# Pmod_8LD.net
KiCad netlist of a schematic drawn in Altium Designer
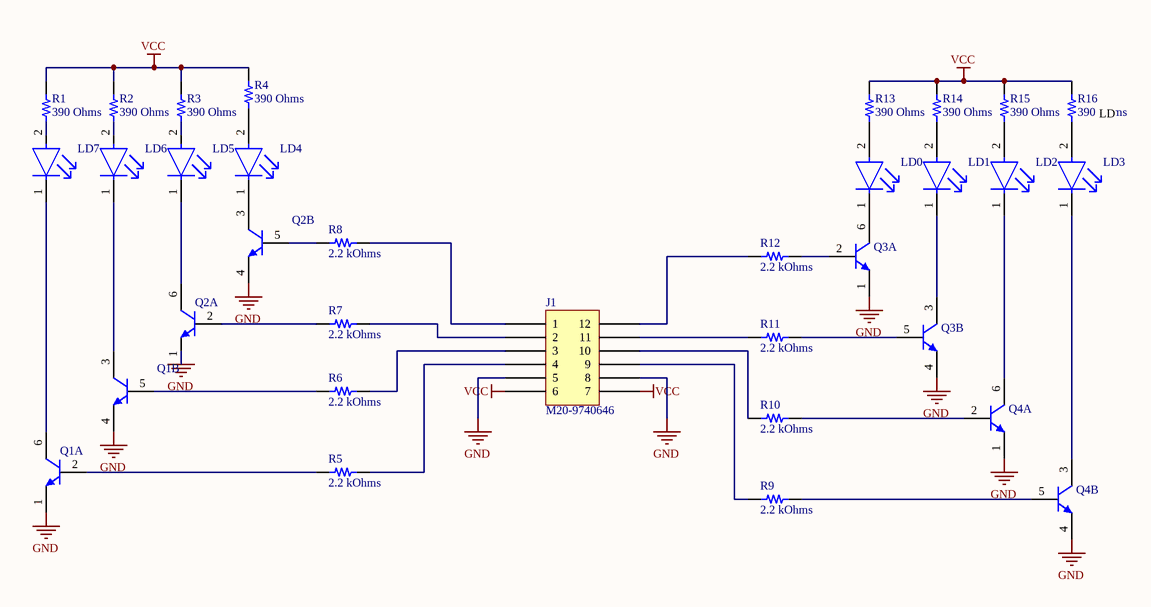
[diagram p0: Pmod_8LD.SchDoc]

(export (version "E")
  (design (tool "Eeschema 10.0.6"))
  (components
    (comp (ref "J1")
      (value "M20-9740646")
      (footprint "HARWIN M20-9740645")
      (description "CONN HEADER R/A 12POS 2.54MM")
      (fields (field (name "MANUFACTURER") "Harwin Inc."))
      (libsource (lib "Celestial Altium Library - altium_library") (part "2X6 PIN DU"))
    )
    (comp (ref "LD0")
      (value "HSMG-C191")
      (footprint "FP-HSMG-C191-MFG")
      (description "LED GREEN DIFFUSED CHIP SMD")
      (fields
        (field (name "MANUFACTURER") "Broadcom")
        (field (name "OCTOPART") "https://octopart.com/hsmg-c191-broadcom-71131308")
      )
      (libsource (lib "Altium Content Vault") (part "8706943c75ba83719d021d2fdc84c58"))
    )
    (comp (ref "LD1")
      (value "HSMG-C191")
      (footprint "FP-HSMG-C191-MFG")
      (description "LED GREEN DIFFUSED CHIP SMD")
      (fields
        (field (name "MANUFACTURER") "Broadcom")
        (field (name "OCTOPART") "https://octopart.com/hsmg-c191-broadcom-71131308")
      )
      (libsource (lib "Altium Content Vault") (part "8706943c75ba83719d021d2fdc84c58"))
    )
    (comp (ref "LD2")
      (value "HSMG-C191")
      (footprint "FP-HSMG-C191-MFG")
      (description "LED GREEN DIFFUSED CHIP SMD")
      (fields
        (field (name "MANUFACTURER") "Broadcom")
        (field (name "OCTOPART") "https://octopart.com/hsmg-c191-broadcom-71131308")
      )
      (libsource (lib "Altium Content Vault") (part "8706943c75ba83719d021d2fdc84c58"))
    )
    (comp (ref "LD3")
      (value "HSMG-C191")
      (footprint "FP-HSMG-C191-MFG")
      (description "LED GREEN DIFFUSED CHIP SMD")
      (fields
        (field (name "MANUFACTURER") "Broadcom")
        (field (name "OCTOPART") "https://octopart.com/hsmg-c191-broadcom-71131308")
      )
      (libsource (lib "Altium Content Vault") (part "8706943c75ba83719d021d2fdc84c58"))
    )
    (comp (ref "LD4")
      (value "HSMG-C191")
      (footprint "FP-HSMG-C191-MFG")
      (description "LED GREEN DIFFUSED CHIP SMD")
      (fields
        (field (name "MANUFACTURER") "Broadcom")
        (field (name "OCTOPART") "https://octopart.com/hsmg-c191-broadcom-71131308")
      )
      (libsource (lib "Altium Content Vault") (part "8706943c75ba83719d021d2fdc84c58"))
    )
    (comp (ref "LD5")
      (value "HSMG-C191")
      (footprint "FP-HSMG-C191-MFG")
      (description "LED GREEN DIFFUSED CHIP SMD")
      (fields
        (field (name "MANUFACTURER") "Broadcom")
        (field (name "OCTOPART") "https://octopart.com/hsmg-c191-broadcom-71131308")
      )
      (libsource (lib "Altium Content Vault") (part "8706943c75ba83719d021d2fdc84c58"))
    )
    (comp (ref "LD6")
      (value "HSMG-C191")
      (footprint "FP-HSMG-C191-MFG")
      (description "LED GREEN DIFFUSED CHIP SMD")
      (fields
        (field (name "MANUFACTURER") "Broadcom")
        (field (name "OCTOPART") "https://octopart.com/hsmg-c191-broadcom-71131308")
      )
      (libsource (lib "Altium Content Vault") (part "8706943c75ba83719d021d2fdc84c58"))
    )
    (comp (ref "LD7")
      (value "HSMG-C191")
      (footprint "FP-HSMG-C191-MFG")
      (description "LED GREEN DIFFUSED CHIP SMD")
      (fields
        (field (name "MANUFACTURER") "Broadcom")
        (field (name "OCTOPART") "https://octopart.com/hsmg-c191-broadcom-71131308")
      )
      (libsource (lib "Altium Content Vault") (part "8706943c75ba83719d021d2fdc84c58"))
    )
    (comp (ref "Q1")
      (value "BC846BDW1T1G")
      (footprint "ONSC-SOT-363-6-419B-02_W_V")
      (description "Dual General Purpose Transistors, NPN, 6-Pin SOT-363, Pb-Free, Tape and Reel")
      (fields (field (name "MANUFACTURER") "On Semiconductor"))
      (libsource (lib "Altium Content Vault") (part "ONSC-NPN_NPN-6_F"))
    )
    (comp (ref "Q2")
      (value "BC846BDW1T1G")
      (footprint "ONSC-SOT-363-6-419B-02_W_V")
      (description "Dual General Purpose Transistors, NPN, 6-Pin SOT-363, Pb-Free, Tape and Reel")
      (fields (field (name "MANUFACTURER") "On Semiconductor"))
      (libsource (lib "Altium Content Vault") (part "ONSC-NPN_NPN-6_F"))
    )
    (comp (ref "Q3")
      (value "BC846BDW1T1G")
      (footprint "ONSC-SOT-363-6-419B-02_W_V")
      (description "Dual General Purpose Transistors, NPN, 6-Pin SOT-363, Pb-Free, Tape and Reel")
      (fields (field (name "MANUFACTURER") "On Semiconductor"))
      (libsource (lib "Altium Content Vault") (part "ONSC-NPN_NPN-6_F"))
    )
    (comp (ref "Q4")
      (value "BC846BDW1T1G")
      (footprint "ONSC-SOT-363-6-419B-02_W_V")
      (description "Dual General Purpose Transistors, NPN, 6-Pin SOT-363, Pb-Free, Tape and Reel")
      (fields (field (name "MANUFACTURER") "On Semiconductor"))
      (libsource (lib "Altium Content Vault") (part "ONSC-NPN_NPN-6_F"))
    )
    (comp (ref "R1")
      (value "390 Ohms")
      (footprint "RES 0805_2012")
      (description "RES SMD 390 OHM 5% 1/8W 0805")
      (fields (field (name "PART NUMBER") "AC0805JR-07390RL") (field (name "MANUFACTURER") "Yageo"))
      (libsource (lib "Celestial Altium Library - altium_library") (part "Resistor"))
    )
    (comp (ref "R2")
      (value "390 Ohms")
      (footprint "RES 0805_2012")
      (description "RES SMD 390 OHM 5% 1/8W 0805")
      (fields (field (name "PART NUMBER") "AC0805JR-07390RL") (field (name "MANUFACTURER") "Yageo"))
      (libsource (lib "Celestial Altium Library - altium_library") (part "Resistor"))
    )
    (comp (ref "R3")
      (value "390 Ohms")
      (footprint "RES 0805_2012")
      (description "RES SMD 390 OHM 5% 1/8W 0805")
      (fields (field (name "PART NUMBER") "AC0805JR-07390RL") (field (name "MANUFACTURER") "Yageo"))
      (libsource (lib "Celestial Altium Library - altium_library") (part "Resistor"))
    )
    (comp (ref "R4")
      (value "390 Ohms")
      (footprint "RES 0805_2012")
      (description "RES SMD 390 OHM 5% 1/8W 0805")
      (fields (field (name "PART NUMBER") "AC0805JR-07390RL") (field (name "MANUFACTURER") "Yageo"))
      (libsource (lib "Celestial Altium Library - altium_library") (part "Resistor"))
    )
    (comp (ref "R5")
      (value "2.2 kOhms")
      (footprint "RES 0805_2012")
      (description "RES SMD 2.2KOHM 0.01% 1/10W 0805")
      (fields (field (name "PART NUMBER") "RG2012L-222-L-T05") (field (name "MANUFACTURER") "Susumu"))
      (libsource (lib "Celestial Altium Library - altium_library") (part "Resistor"))
    )
    (comp (ref "R6")
      (value "2.2 kOhms")
      (footprint "RES 0805_2012")
      (description "RES SMD 2.2KOHM 0.01% 1/10W 0805")
      (fields (field (name "PART NUMBER") "RG2012L-222-L-T05") (field (name "MANUFACTURER") "Susumu"))
      (libsource (lib "Celestial Altium Library - altium_library") (part "Resistor"))
    )
    (comp (ref "R7")
      (value "2.2 kOhms")
      (footprint "RES 0805_2012")
      (description "RES SMD 2.2KOHM 0.01% 1/10W 0805")
      (fields (field (name "PART NUMBER") "RG2012L-222-L-T05") (field (name "MANUFACTURER") "Susumu"))
      (libsource (lib "Celestial Altium Library - altium_library") (part "Resistor"))
    )
    (comp (ref "R8")
      (value "2.2 kOhms")
      (footprint "RES 0805_2012")
      (description "RES SMD 2.2KOHM 0.01% 1/10W 0805")
      (fields (field (name "PART NUMBER") "RG2012L-222-L-T05") (field (name "MANUFACTURER") "Susumu"))
      (libsource (lib "Celestial Altium Library - altium_library") (part "Resistor"))
    )
    (comp (ref "R9")
      (value "2.2 kOhms")
      (footprint "RES 0805_2012")
      (description "RES SMD 2.2KOHM 0.01% 1/10W 0805")
      (fields (field (name "PART NUMBER") "RG2012L-222-L-T05") (field (name "MANUFACTURER") "Susumu"))
      (libsource (lib "Celestial Altium Library - altium_library") (part "Resistor"))
    )
    (comp (ref "R10")
      (value "2.2 kOhms")
      (footprint "RES 0805_2012")
      (description "RES SMD 2.2KOHM 0.01% 1/10W 0805")
      (fields (field (name "PART NUMBER") "RG2012L-222-L-T05") (field (name "MANUFACTURER") "Susumu"))
      (libsource (lib "Celestial Altium Library - altium_library") (part "Resistor"))
    )
    (comp (ref "R11")
      (value "2.2 kOhms")
      (footprint "RES 0805_2012")
      (description "RES SMD 2.2KOHM 0.01% 1/10W 0805")
      (fields (field (name "PART NUMBER") "RG2012L-222-L-T05") (field (name "MANUFACTURER") "Susumu"))
      (libsource (lib "Celestial Altium Library - altium_library") (part "Resistor"))
    )
    (comp (ref "R12")
      (value "2.2 kOhms")
      (footprint "RES 0805_2012")
      (description "RES SMD 2.2KOHM 0.01% 1/10W 0805")
      (fields (field (name "PART NUMBER") "RG2012L-222-L-T05") (field (name "MANUFACTURER") "Susumu"))
      (libsource (lib "Celestial Altium Library - altium_library") (part "Resistor"))
    )
    (comp (ref "R13")
      (value "390 Ohms")
      (footprint "RES 0805_2012")
      (description "RES SMD 390 OHM 5% 1/8W 0805")
      (fields (field (name "PART NUMBER") "AC0805JR-07390RL") (field (name "MANUFACTURER") "Yageo"))
      (libsource (lib "Celestial Altium Library - altium_library") (part "Resistor"))
    )
    (comp (ref "R14")
      (value "390 Ohms")
      (footprint "RES 0805_2012")
      (description "RES SMD 390 OHM 5% 1/8W 0805")
      (fields (field (name "PART NUMBER") "AC0805JR-07390RL") (field (name "MANUFACTURER") "Yageo"))
      (libsource (lib "Celestial Altium Library - altium_library") (part "Resistor"))
    )
    (comp (ref "R15")
      (value "390 Ohms")
      (footprint "RES 0805_2012")
      (description "RES SMD 390 OHM 5% 1/8W 0805")
      (fields (field (name "PART NUMBER") "AC0805JR-07390RL") (field (name "MANUFACTURER") "Yageo"))
      (libsource (lib "Celestial Altium Library - altium_library") (part "Resistor"))
    )
    (comp (ref "R16")
      (value "390 Ohms")
      (footprint "RES 0805_2012")
      (description "RES SMD 390 OHM 5% 1/8W 0805")
      (fields (field (name "PART NUMBER") "AC0805JR-07390RL") (field (name "MANUFACTURER") "Yageo"))
      (libsource (lib "Celestial Altium Library - altium_library") (part "Resistor"))
    )
  )
  (nets
    (net (code "1") (name "GND") (class "Default")
      (node (ref "J1") (pin "5") (pinfunction "5_5") (pintype "passive"))
      (node (ref "J1") (pin "8") (pinfunction "8_8") (pintype "passive"))
      (node (ref "Q1") (pin "1") (pinfunction "E_1") (pintype "passive"))
      (node (ref "Q1") (pin "4") (pinfunction "E_4") (pintype "passive"))
      (node (ref "Q2") (pin "1") (pinfunction "E_1") (pintype "passive"))
      (node (ref "Q2") (pin "4") (pinfunction "E_4") (pintype "passive"))
      (node (ref "Q3") (pin "1") (pinfunction "E_1") (pintype "passive"))
      (node (ref "Q3") (pin "4") (pinfunction "E_4") (pintype "passive"))
      (node (ref "Q4") (pin "1") (pinfunction "E_1") (pintype "passive"))
      (node (ref "Q4") (pin "4") (pinfunction "E_4") (pintype "passive"))
    )
    (net (code "2") (name "Net-(J1-Pad1)") (class "Default")
      (node (ref "J1") (pin "1") (pinfunction "1_1") (pintype "passive"))
      (node (ref "R8") (pin "1") (pinfunction "1_1") (pintype "passive"))
    )
    (net (code "3") (name "Net-(J1-Pad2)") (class "Default")
      (node (ref "J1") (pin "2") (pinfunction "2_2") (pintype "passive"))
      (node (ref "R7") (pin "1") (pinfunction "1_1") (pintype "passive"))
    )
    (net (code "4") (name "Net-(J1-Pad3)") (class "Default")
      (node (ref "J1") (pin "3") (pinfunction "3_3") (pintype "passive"))
      (node (ref "R6") (pin "1") (pinfunction "1_1") (pintype "passive"))
    )
    (net (code "5") (name "Net-(J1-Pad4)") (class "Default")
      (node (ref "J1") (pin "4") (pinfunction "4_4") (pintype "passive"))
      (node (ref "R5") (pin "1") (pinfunction "1_1") (pintype "passive"))
    )
    (net (code "6") (name "Net-(J1-Pad9)") (class "Default")
      (node (ref "J1") (pin "9") (pinfunction "9_9") (pintype "passive"))
      (node (ref "R9") (pin "2") (pinfunction "2_2") (pintype "passive"))
    )
    (net (code "7") (name "Net-(J1-Pad10)") (class "Default")
      (node (ref "J1") (pin "10") (pinfunction "10_10") (pintype "passive"))
      (node (ref "R10") (pin "2") (pinfunction "2_2") (pintype "passive"))
    )
    (net (code "8") (name "Net-(J1-Pad11)") (class "Default")
      (node (ref "J1") (pin "11") (pinfunction "11_11") (pintype "passive"))
      (node (ref "R11") (pin "2") (pinfunction "2_2") (pintype "passive"))
    )
    (net (code "9") (name "Net-(J1-Pad12)") (class "Default")
      (node (ref "J1") (pin "12") (pinfunction "12_12") (pintype "passive"))
      (node (ref "R12") (pin "2") (pinfunction "2_2") (pintype "passive"))
    )
    (net (code "10") (name "Net-(LD0-A)") (class "Default")
      (node (ref "LD0") (pin "2") (pinfunction "A_2") (pintype "passive"))
      (node (ref "R13") (pin "2") (pinfunction "2_2") (pintype "passive"))
    )
    (net (code "11") (name "Net-(LD0-C)") (class "Default")
      (node (ref "LD0") (pin "1") (pinfunction "C_1") (pintype "passive"))
      (node (ref "Q3") (pin "6") (pinfunction "C_6") (pintype "passive"))
    )
    (net (code "12") (name "Net-(LD1-A)") (class "Default")
      (node (ref "LD1") (pin "2") (pinfunction "A_2") (pintype "passive"))
      (node (ref "R14") (pin "2") (pinfunction "2_2") (pintype "passive"))
    )
    (net (code "13") (name "Net-(LD1-C)") (class "Default")
      (node (ref "LD1") (pin "1") (pinfunction "C_1") (pintype "passive"))
      (node (ref "Q3") (pin "3") (pinfunction "C_3") (pintype "passive"))
    )
    (net (code "14") (name "Net-(LD2-A)") (class "Default")
      (node (ref "LD2") (pin "2") (pinfunction "A_2") (pintype "passive"))
      (node (ref "R15") (pin "2") (pinfunction "2_2") (pintype "passive"))
    )
    (net (code "15") (name "Net-(LD2-C)") (class "Default")
      (node (ref "LD2") (pin "1") (pinfunction "C_1") (pintype "passive"))
      (node (ref "Q4") (pin "6") (pinfunction "C_6") (pintype "passive"))
    )
    (net (code "16") (name "Net-(LD3-A)") (class "Default")
      (node (ref "LD3") (pin "2") (pinfunction "A_2") (pintype "passive"))
      (node (ref "R16") (pin "2") (pinfunction "2_2") (pintype "passive"))
    )
    (net (code "17") (name "Net-(LD3-C)") (class "Default")
      (node (ref "LD3") (pin "1") (pinfunction "C_1") (pintype "passive"))
      (node (ref "Q4") (pin "3") (pinfunction "C_3") (pintype "passive"))
    )
    (net (code "18") (name "Net-(LD4-A)") (class "Default")
      (node (ref "LD4") (pin "2") (pinfunction "A_2") (pintype "passive"))
      (node (ref "R4") (pin "2") (pinfunction "2_2") (pintype "passive"))
    )
    (net (code "19") (name "Net-(LD4-C)") (class "Default")
      (node (ref "LD4") (pin "1") (pinfunction "C_1") (pintype "passive"))
      (node (ref "Q2") (pin "3") (pinfunction "C_3") (pintype "passive"))
    )
    (net (code "20") (name "Net-(LD5-A)") (class "Default")
      (node (ref "LD5") (pin "2") (pinfunction "A_2") (pintype "passive"))
      (node (ref "R3") (pin "2") (pinfunction "2_2") (pintype "passive"))
    )
    (net (code "21") (name "Net-(LD5-C)") (class "Default")
      (node (ref "LD5") (pin "1") (pinfunction "C_1") (pintype "passive"))
      (node (ref "Q2") (pin "6") (pinfunction "C_6") (pintype "passive"))
    )
    (net (code "22") (name "Net-(LD6-A)") (class "Default")
      (node (ref "LD6") (pin "2") (pinfunction "A_2") (pintype "passive"))
      (node (ref "R2") (pin "2") (pinfunction "2_2") (pintype "passive"))
    )
    (net (code "23") (name "Net-(LD6-C)") (class "Default")
      (node (ref "LD6") (pin "1") (pinfunction "C_1") (pintype "passive"))
      (node (ref "Q1") (pin "3") (pinfunction "C_3") (pintype "passive"))
    )
    (net (code "24") (name "Net-(LD7-A)") (class "Default")
      (node (ref "LD7") (pin "2") (pinfunction "A_2") (pintype "passive"))
      (node (ref "R1") (pin "2") (pinfunction "2_2") (pintype "passive"))
    )
    (net (code "25") (name "Net-(LD7-C)") (class "Default")
      (node (ref "LD7") (pin "1") (pinfunction "C_1") (pintype "passive"))
      (node (ref "Q1") (pin "6") (pinfunction "C_6") (pintype "passive"))
    )
    (net (code "26") (name "Net-(Q1A-B)") (class "Default")
      (node (ref "Q1") (pin "2") (pinfunction "B_2") (pintype "passive"))
      (node (ref "R5") (pin "2") (pinfunction "2_2") (pintype "passive"))
    )
    (net (code "27") (name "Net-(Q1B-B)") (class "Default")
      (node (ref "Q1") (pin "5") (pinfunction "B_5") (pintype "passive"))
      (node (ref "R6") (pin "2") (pinfunction "2_2") (pintype "passive"))
    )
    (net (code "28") (name "Net-(Q2A-B)") (class "Default")
      (node (ref "Q2") (pin "2") (pinfunction "B_2") (pintype "passive"))
      (node (ref "R7") (pin "2") (pinfunction "2_2") (pintype "passive"))
    )
    (net (code "29") (name "Net-(Q2B-B)") (class "Default")
      (node (ref "Q2") (pin "5") (pinfunction "B_5") (pintype "passive"))
      (node (ref "R8") (pin "2") (pinfunction "2_2") (pintype "passive"))
    )
    (net (code "30") (name "Net-(Q3A-B)") (class "Default")
      (node (ref "Q3") (pin "2") (pinfunction "B_2") (pintype "passive"))
      (node (ref "R12") (pin "1") (pinfunction "1_1") (pintype "passive"))
    )
    (net (code "31") (name "Net-(Q3B-B)") (class "Default")
      (node (ref "Q3") (pin "5") (pinfunction "B_5") (pintype "passive"))
      (node (ref "R11") (pin "1") (pinfunction "1_1") (pintype "passive"))
    )
    (net (code "32") (name "Net-(Q4A-B)") (class "Default")
      (node (ref "Q4") (pin "2") (pinfunction "B_2") (pintype "passive"))
      (node (ref "R10") (pin "1") (pinfunction "1_1") (pintype "passive"))
    )
    (net (code "33") (name "Net-(Q4B-B)") (class "Default")
      (node (ref "Q4") (pin "5") (pinfunction "B_5") (pintype "passive"))
      (node (ref "R9") (pin "1") (pinfunction "1_1") (pintype "passive"))
    )
    (net (code "34") (name "VCC") (class "Default")
      (node (ref "J1") (pin "6") (pinfunction "6_6") (pintype "passive"))
      (node (ref "J1") (pin "7") (pinfunction "7_7") (pintype "passive"))
      (node (ref "R1") (pin "1") (pinfunction "1_1") (pintype "passive"))
      (node (ref "R13") (pin "1") (pinfunction "1_1") (pintype "passive"))
      (node (ref "R14") (pin "1") (pinfunction "1_1") (pintype "passive"))
      (node (ref "R15") (pin "1") (pinfunction "1_1") (pintype "passive"))
      (node (ref "R16") (pin "1") (pinfunction "1_1") (pintype "passive"))
      (node (ref "R2") (pin "1") (pinfunction "1_1") (pintype "passive"))
      (node (ref "R3") (pin "1") (pinfunction "1_1") (pintype "passive"))
      (node (ref "R4") (pin "1") (pinfunction "1_1") (pintype "passive"))
    )
  )
)
